# mrShark_Adapter.net
KiCad netlist of a schematic drawn in EAGLE
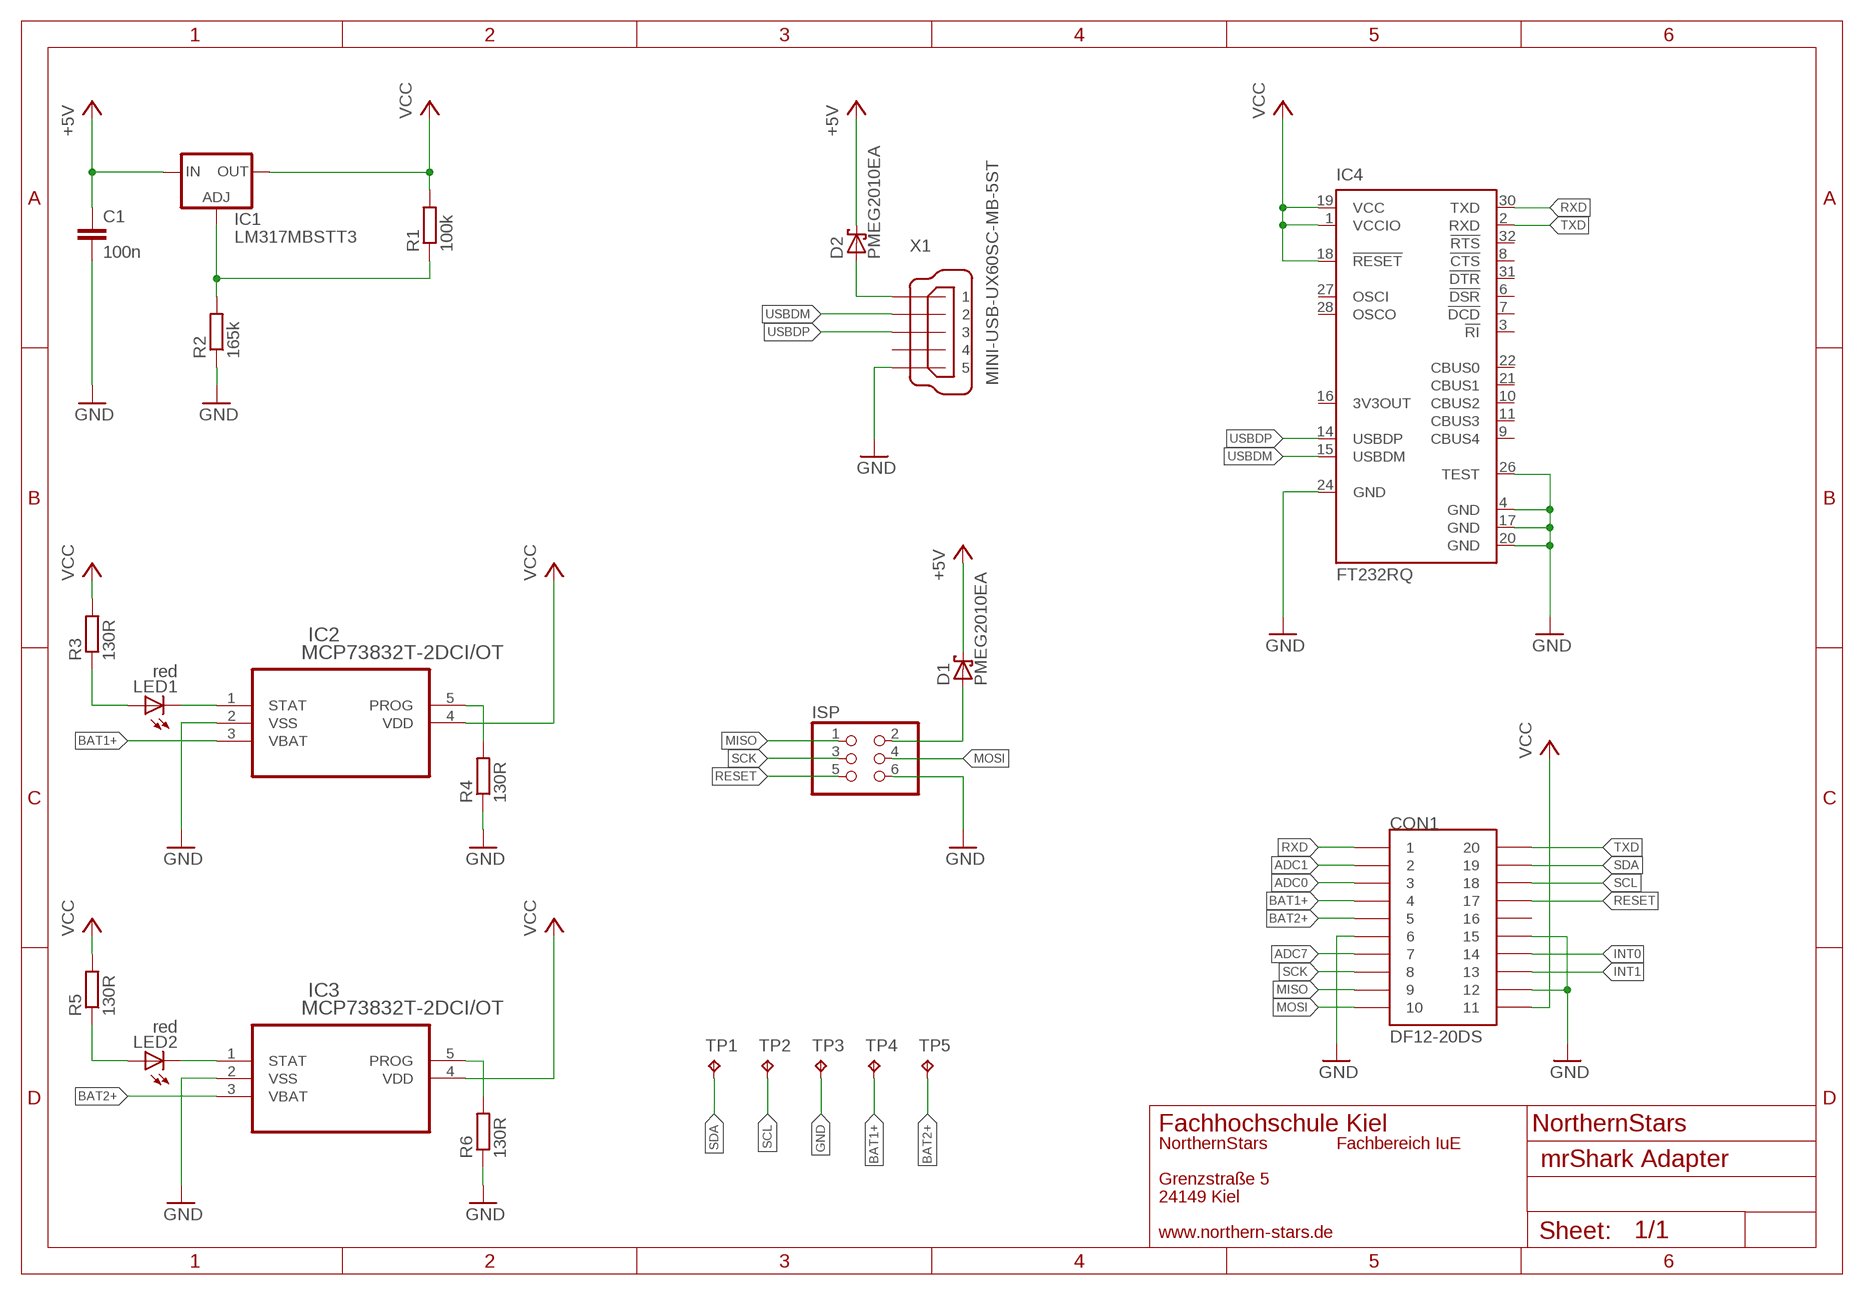
[diagram p0: schematic, sheet 1]

(export (version "E")
  (design (tool "Eeschema 10.0.6"))
  (components
    (comp (ref "C1")
      (value "100n")
      (footprint "eagle-import:C0603")
      (libsource (lib "eagle-import") (part "C-EUC0603"))
    )
    (comp (ref "CON1")
      (value "DF12-20DS")
      (footprint "eagle-import:DF12-20DS")
      (libsource (lib "eagle-import") (part "DF12-20DS"))
    )
    (comp (ref "D1")
      (value "PMEG2010EA")
      (footprint "eagle-import:SOD323-R")
      (libsource (lib "eagle-import") (part "PMEG2010EAR"))
    )
    (comp (ref "D2")
      (value "PMEG2010EA")
      (footprint "eagle-import:SOD323-R")
      (libsource (lib "eagle-import") (part "PMEG2010EAR"))
    )
    (comp (ref "IC1")
      (value "LM317MBSTT3")
      (footprint "eagle-import:SOT223")
      (libsource (lib "eagle-import") (part "LM317?MBSTT3"))
    )
    (comp (ref "IC2")
      (value "MCP73832T-2DCI/OT")
      (footprint "eagle-import:SOT95P300X145-5N")
      (libsource (lib "eagle-import") (part "MCP73832T-2DCI/OT"))
    )
    (comp (ref "IC3")
      (value "MCP73832T-2DCI/OT")
      (footprint "eagle-import:SOT95P300X145-5N")
      (libsource (lib "eagle-import") (part "MCP73832T-2DCI/OT"))
    )
    (comp (ref "IC4")
      (value "FT232RQ")
      (footprint "eagle-import:QFN32")
      (libsource (lib "eagle-import") (part "FT232RQ"))
    )
    (comp (ref "ISP")
      (value "PINHD-2X03_2.54-SMD")
      (footprint "eagle-import:2X03SMD")
      (libsource (lib "eagle-import") (part "PINHD-2X03_2.54-SMD"))
    )
    (comp (ref "LED1")
      (value "red")
      (footprint "eagle-import:CHIP-LED0603")
      (libsource (lib "eagle-import") (part "LEDCHIP-LED0603"))
    )
    (comp (ref "LED2")
      (value "red")
      (footprint "eagle-import:CHIP-LED0603")
      (libsource (lib "eagle-import") (part "LEDCHIP-LED0603"))
    )
    (comp (ref "R1")
      (value "100k")
      (footprint "eagle-import:R0603")
      (libsource (lib "eagle-import") (part "R-EU_R0603"))
    )
    (comp (ref "R2")
      (value "165k")
      (footprint "eagle-import:R0603")
      (libsource (lib "eagle-import") (part "R-EU_R0603"))
    )
    (comp (ref "R3")
      (value "130R")
      (footprint "eagle-import:R0603")
      (libsource (lib "eagle-import") (part "R-EU_R0603"))
    )
    (comp (ref "R4")
      (value "130R")
      (footprint "eagle-import:R0603")
      (libsource (lib "eagle-import") (part "R-EU_R0603"))
    )
    (comp (ref "R5")
      (value "130R")
      (footprint "eagle-import:R0603")
      (libsource (lib "eagle-import") (part "R-EU_R0603"))
    )
    (comp (ref "R6")
      (value "130R")
      (footprint "eagle-import:R0603")
      (libsource (lib "eagle-import") (part "R-EU_R0603"))
    )
    (comp (ref "TP1")
      (value "TPTP06SQ")
      (footprint "eagle-import:TP06SQ")
      (libsource (lib "eagle-import") (part "TPTP06SQ"))
    )
    (comp (ref "TP2")
      (value "TPTP06SQ")
      (footprint "eagle-import:TP06SQ")
      (libsource (lib "eagle-import") (part "TPTP06SQ"))
    )
    (comp (ref "TP3")
      (value "TPTP06SQ")
      (footprint "eagle-import:TP06SQ")
      (libsource (lib "eagle-import") (part "TPTP06SQ"))
    )
    (comp (ref "TP4")
      (value "TPTP06SQ")
      (footprint "eagle-import:TP06SQ")
      (libsource (lib "eagle-import") (part "TPTP06SQ"))
    )
    (comp (ref "TP5")
      (value "TPTP06SQ")
      (footprint "eagle-import:TP06SQ")
      (libsource (lib "eagle-import") (part "TPTP06SQ"))
    )
    (comp (ref "X1")
      (value "MINI-USB-UX60SC-MB-5ST")
      (footprint "eagle-import:UX60SC-MB-5ST")
      (libsource (lib "eagle-import") (part "MINI-USB-UX60SC-MB-5ST"))
    )
  )
  (nets
    (net (code "1") (name "+5V") (class "Default")
      (node (ref "C1") (pin "1") (pinfunction "1_1") (pintype "passive"))
      (node (ref "D1") (pin "C") (pinfunction "C_C") (pintype "passive"))
      (node (ref "D2") (pin "C") (pinfunction "C_C") (pintype "passive"))
      (node (ref "IC1") (pin "3") (pinfunction "IN_3") (pintype "input"))
    )
    (net (code "2") (name "ADC0") (class "Default")
      (node (ref "CON1") (pin "3") (pinfunction "3_3") (pintype "bidirectional"))
    )
    (net (code "3") (name "ADC1") (class "Default")
      (node (ref "CON1") (pin "2") (pinfunction "2_2") (pintype "bidirectional"))
    )
    (net (code "4") (name "ADC7") (class "Default")
      (node (ref "CON1") (pin "7") (pinfunction "7_7") (pintype "bidirectional"))
    )
    (net (code "5") (name "BAT1+") (class "Default")
      (node (ref "CON1") (pin "4") (pinfunction "4_4") (pintype "bidirectional"))
      (node (ref "IC2") (pin "3") (pinfunction "VBAT_3") (pintype "input"))
      (node (ref "TP4") (pin "TP") (pinfunction "TP_TP") (pintype "input"))
    )
    (net (code "6") (name "BAT2+") (class "Default")
      (node (ref "CON1") (pin "5") (pinfunction "5_5") (pintype "bidirectional"))
      (node (ref "IC3") (pin "3") (pinfunction "VBAT_3") (pintype "input"))
      (node (ref "TP5") (pin "TP") (pinfunction "TP_TP") (pintype "input"))
    )
    (net (code "7") (name "GND") (class "Default")
      (node (ref "C1") (pin "2") (pinfunction "2_2") (pintype "passive"))
      (node (ref "CON1") (pin "12") (pinfunction "12_12") (pintype "bidirectional"))
      (node (ref "CON1") (pin "15") (pinfunction "15_15") (pintype "bidirectional"))
      (node (ref "CON1") (pin "6") (pinfunction "6_6") (pintype "bidirectional"))
      (node (ref "IC2") (pin "2") (pinfunction "VSS_2") (pintype "passive"))
      (node (ref "IC3") (pin "2") (pinfunction "VSS_2") (pintype "passive"))
      (node (ref "IC4") (pin "17") (pinfunction "GND_17") (pintype "power_in"))
      (node (ref "IC4") (pin "20") (pinfunction "GND_20") (pintype "power_in"))
      (node (ref "IC4") (pin "24") (pinfunction "GND_24") (pintype "power_in"))
      (node (ref "IC4") (pin "26") (pinfunction "TEST_26") (pintype "input"))
      (node (ref "IC4") (pin "4") (pinfunction "GND_4") (pintype "power_in"))
      (node (ref "ISP") (pin "6") (pinfunction "6_6") (pintype "passive"))
      (node (ref "R2") (pin "1") (pinfunction "1_1") (pintype "passive"))
      (node (ref "R4") (pin "1") (pinfunction "1_1") (pintype "passive"))
      (node (ref "R6") (pin "1") (pinfunction "1_1") (pintype "passive"))
      (node (ref "TP3") (pin "TP") (pinfunction "TP_TP") (pintype "input"))
      (node (ref "X1") (pin "5") (pinfunction "5_5") (pintype "input"))
    )
    (net (code "8") (name "INT0") (class "Default")
      (node (ref "CON1") (pin "14") (pinfunction "14_14") (pintype "bidirectional"))
    )
    (net (code "9") (name "INT1") (class "Default")
      (node (ref "CON1") (pin "13") (pinfunction "13_13") (pintype "bidirectional"))
    )
    (net (code "10") (name "MISO") (class "Default")
      (node (ref "CON1") (pin "9") (pinfunction "9_9") (pintype "bidirectional"))
      (node (ref "ISP") (pin "1") (pinfunction "1_1") (pintype "passive"))
    )
    (net (code "11") (name "MOSI") (class "Default")
      (node (ref "CON1") (pin "10") (pinfunction "10_10") (pintype "bidirectional"))
      (node (ref "ISP") (pin "4") (pinfunction "4_4") (pintype "passive"))
    )
    (net (code "12") (name "Net-(D1-PadA)") (class "Default")
      (node (ref "D1") (pin "A") (pinfunction "A_A") (pintype "passive"))
      (node (ref "ISP") (pin "2") (pinfunction "2_2") (pintype "passive"))
    )
    (net (code "13") (name "Net-(D2-PadA)") (class "Default")
      (node (ref "D2") (pin "A") (pinfunction "A_A") (pintype "passive"))
      (node (ref "X1") (pin "1") (pinfunction "1_1") (pintype "input"))
    )
    (net (code "14") (name "Net-(IC1-ADJ)") (class "Default")
      (node (ref "IC1") (pin "1") (pinfunction "ADJ_1") (pintype "input"))
      (node (ref "R1") (pin "1") (pinfunction "1_1") (pintype "passive"))
      (node (ref "R2") (pin "2") (pinfunction "2_2") (pintype "passive"))
    )
    (net (code "15") (name "Net-(IC2-PROG)") (class "Default")
      (node (ref "IC2") (pin "5") (pinfunction "PROG_5") (pintype "input"))
      (node (ref "R4") (pin "2") (pinfunction "2_2") (pintype "passive"))
    )
    (net (code "16") (name "Net-(IC2-STAT)") (class "Default")
      (node (ref "IC2") (pin "1") (pinfunction "STAT_1") (pintype "input"))
      (node (ref "LED1") (pin "C") (pinfunction "C_C") (pintype "passive"))
    )
    (net (code "17") (name "Net-(IC3-PROG)") (class "Default")
      (node (ref "IC3") (pin "5") (pinfunction "PROG_5") (pintype "input"))
      (node (ref "R6") (pin "2") (pinfunction "2_2") (pintype "passive"))
    )
    (net (code "18") (name "Net-(IC3-STAT)") (class "Default")
      (node (ref "IC3") (pin "1") (pinfunction "STAT_1") (pintype "input"))
      (node (ref "LED2") (pin "C") (pinfunction "C_C") (pintype "passive"))
    )
    (net (code "19") (name "Net-(LED1-PadA)") (class "Default")
      (node (ref "LED1") (pin "A") (pinfunction "A_A") (pintype "passive"))
      (node (ref "R3") (pin "1") (pinfunction "1_1") (pintype "passive"))
    )
    (net (code "20") (name "Net-(LED2-PadA)") (class "Default")
      (node (ref "LED2") (pin "A") (pinfunction "A_A") (pintype "passive"))
      (node (ref "R5") (pin "1") (pinfunction "1_1") (pintype "passive"))
    )
    (net (code "21") (name "RESET") (class "Default")
      (node (ref "CON1") (pin "17") (pinfunction "17_17") (pintype "bidirectional"))
      (node (ref "ISP") (pin "5") (pinfunction "5_5") (pintype "passive"))
    )
    (net (code "22") (name "RXD") (class "Default")
      (node (ref "CON1") (pin "1") (pinfunction "1_1") (pintype "bidirectional"))
      (node (ref "IC4") (pin "30") (pinfunction "TXD_30") (pintype "output"))
    )
    (net (code "23") (name "SCK") (class "Default")
      (node (ref "CON1") (pin "8") (pinfunction "8_8") (pintype "bidirectional"))
      (node (ref "ISP") (pin "3") (pinfunction "3_3") (pintype "passive"))
    )
    (net (code "24") (name "SCL") (class "Default")
      (node (ref "CON1") (pin "18") (pinfunction "18_18") (pintype "bidirectional"))
      (node (ref "TP2") (pin "TP") (pinfunction "TP_TP") (pintype "input"))
    )
    (net (code "25") (name "SDA") (class "Default")
      (node (ref "CON1") (pin "19") (pinfunction "19_19") (pintype "bidirectional"))
      (node (ref "TP1") (pin "TP") (pinfunction "TP_TP") (pintype "input"))
    )
    (net (code "26") (name "TXD") (class "Default")
      (node (ref "CON1") (pin "20") (pinfunction "20_20") (pintype "bidirectional"))
      (node (ref "IC4") (pin "2") (pinfunction "RXD_2") (pintype "input"))
    )
    (net (code "27") (name "USBDM") (class "Default")
      (node (ref "IC4") (pin "15") (pinfunction "USBDM_15") (pintype "bidirectional"))
      (node (ref "X1") (pin "2") (pinfunction "2_2") (pintype "input"))
    )
    (net (code "28") (name "USBDP") (class "Default")
      (node (ref "IC4") (pin "14") (pinfunction "USBDP_14") (pintype "bidirectional"))
      (node (ref "X1") (pin "3") (pinfunction "3_3") (pintype "input"))
    )
    (net (code "29") (name "VCC") (class "Default")
      (node (ref "CON1") (pin "11") (pinfunction "11_11") (pintype "bidirectional"))
      (node (ref "IC1") (pin "4") (pinfunction "OUT_4") (pintype "passive"))
      (node (ref "IC2") (pin "4") (pinfunction "VDD_4") (pintype "power_in"))
      (node (ref "IC3") (pin "4") (pinfunction "VDD_4") (pintype "power_in"))
      (node (ref "IC4") (pin "1") (pinfunction "VCCIO_1") (pintype "power_in"))
      (node (ref "IC4") (pin "18") (pinfunction "~{RESET}_18") (pintype "input"))
      (node (ref "IC4") (pin "19") (pinfunction "VCC_19") (pintype "power_in"))
      (node (ref "R1") (pin "2") (pinfunction "2_2") (pintype "passive"))
      (node (ref "R3") (pin "2") (pinfunction "2_2") (pintype "passive"))
      (node (ref "R5") (pin "2") (pinfunction "2_2") (pintype "passive"))
    )
    (net (code "30") (name "unconnected-(CON1-Pad16)") (class "Default")
      (node (ref "CON1") (pin "16") (pinfunction "16_16") (pintype "bidirectional"))
    )
    (net (code "31") (name "unconnected-(IC4-3V3OUT-Pad16)") (class "Default")
      (node (ref "IC4") (pin "16") (pinfunction "3V3OUT_16") (pintype "output"))
    )
    (net (code "32") (name "unconnected-(IC4-CBUS0-Pad22)") (class "Default")
      (node (ref "IC4") (pin "22") (pinfunction "CBUS0_22") (pintype "bidirectional"))
    )
    (net (code "33") (name "unconnected-(IC4-CBUS1-Pad21)") (class "Default")
      (node (ref "IC4") (pin "21") (pinfunction "CBUS1_21") (pintype "bidirectional"))
    )
    (net (code "34") (name "unconnected-(IC4-CBUS2-Pad10)") (class "Default")
      (node (ref "IC4") (pin "10") (pinfunction "CBUS2_10") (pintype "bidirectional"))
    )
    (net (code "35") (name "unconnected-(IC4-CBUS3-Pad11)") (class "Default")
      (node (ref "IC4") (pin "11") (pinfunction "CBUS3_11") (pintype "bidirectional"))
    )
    (net (code "36") (name "unconnected-(IC4-CBUS4-Pad9)") (class "Default")
      (node (ref "IC4") (pin "9") (pinfunction "CBUS4_9") (pintype "bidirectional"))
    )
    (net (code "37") (name "unconnected-(IC4-OSCI-Pad27)") (class "Default")
      (node (ref "IC4") (pin "27") (pinfunction "OSCI_27") (pintype "input"))
    )
    (net (code "38") (name "unconnected-(IC4-OSCO-Pad28)") (class "Default")
      (node (ref "IC4") (pin "28") (pinfunction "OSCO_28") (pintype "output"))
    )
    (net (code "39") (name "unconnected-(IC4-~{CTS}-Pad8)") (class "Default")
      (node (ref "IC4") (pin "8") (pinfunction "~{CTS}_8") (pintype "input"))
    )
    (net (code "40") (name "unconnected-(IC4-~{DCD}-Pad7)") (class "Default")
      (node (ref "IC4") (pin "7") (pinfunction "~{DCD}_7") (pintype "input"))
    )
    (net (code "41") (name "unconnected-(IC4-~{DSR}-Pad6)") (class "Default")
      (node (ref "IC4") (pin "6") (pinfunction "~{DSR}_6") (pintype "input"))
    )
    (net (code "42") (name "unconnected-(IC4-~{DTR}-Pad31)") (class "Default")
      (node (ref "IC4") (pin "31") (pinfunction "~{DTR}_31") (pintype "output"))
    )
    (net (code "43") (name "unconnected-(IC4-~{RI}-Pad3)") (class "Default")
      (node (ref "IC4") (pin "3") (pinfunction "~{RI}_3") (pintype "input"))
    )
    (net (code "44") (name "unconnected-(IC4-~{RTS}-Pad32)") (class "Default")
      (node (ref "IC4") (pin "32") (pinfunction "~{RTS}_32") (pintype "output"))
    )
    (net (code "45") (name "unconnected-(X1-Pad4)") (class "Default")
      (node (ref "X1") (pin "4") (pinfunction "4_4") (pintype "input"))
    )
  )
)
